# Pyr0-Piezo_SingleDisk_Adapter_3pin.net
KiCad netlist of a schematic drawn in EAGLE
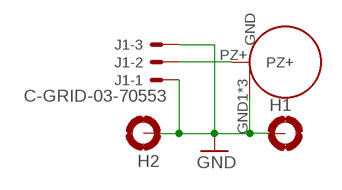
[diagram p0: schematic, sheet 1]

(export (version "E")
  (design (tool "Eeschema 10.0.6"))
  (components
    (comp (ref "H1")
      (value "HOLES_MOUNT-PAD-ROUND3.2")
      (footprint "eagle-import:HOLES_3,2-PAD")
      (libsource (lib "eagle-import") (part "HOLES_MOUNT-PAD-ROUND3.2"))
    )
    (comp (ref "H2")
      (value "HOLES_MOUNT-PAD-ROUND3.2")
      (footprint "eagle-import:HOLES_3,2-PAD")
      (libsource (lib "eagle-import") (part "HOLES_MOUNT-PAD-ROUND3.2"))
    )
    (comp (ref "J1")
      (value "C-GRID-03-70553")
      (footprint "eagle-import:70553-03")
      (fields (field (name "MF") "MOLEX"))
      (libsource (lib "eagle-import") (part "C-GRID-03-70553"))
    )
    (comp (ref "PZ1")
      (value "PIEZO-DISK12MM-OFFSET")
      (footprint "eagle-import:PIEZO-DISK-12MM-OFFSET")
      (libsource (lib "eagle-import") (part "PIEZO-DISK12MM-OFFSET"))
    )
  )
  (nets
    (net (code "1") (name "GND") (class "Default")
      (node (ref "H1") (pin "B3,2") (pinfunction "MOUNT_B3,2") (pintype "passive"))
      (node (ref "H2") (pin "B3,2") (pinfunction "MOUNT_B3,2") (pintype "passive"))
      (node (ref "J1") (pin "1") (pinfunction "S_1") (pintype "passive"))
      (node (ref "J1") (pin "3") (pinfunction "S_3") (pintype "passive"))
      (node (ref "PZ1") (pin "GND1") (pinfunction "GND_GND1") (pintype "passive"))
      (node (ref "PZ1") (pin "GND2") (pinfunction "GND_GND2") (pintype "passive"))
      (node (ref "PZ1") (pin "GND3") (pinfunction "GND_GND3") (pintype "passive"))
    )
    (net (code "2") (name "Net-(J1B-S)") (class "Default")
      (node (ref "J1") (pin "2") (pinfunction "S_2") (pintype "passive"))
      (node (ref "PZ1") (pin "PZ+") (pinfunction "PZ+_PZ+") (pintype "bidirectional"))
    )
  )
)
